# Shutdown_Circuit.net
KiCad netlist of a schematic drawn in EAGLE
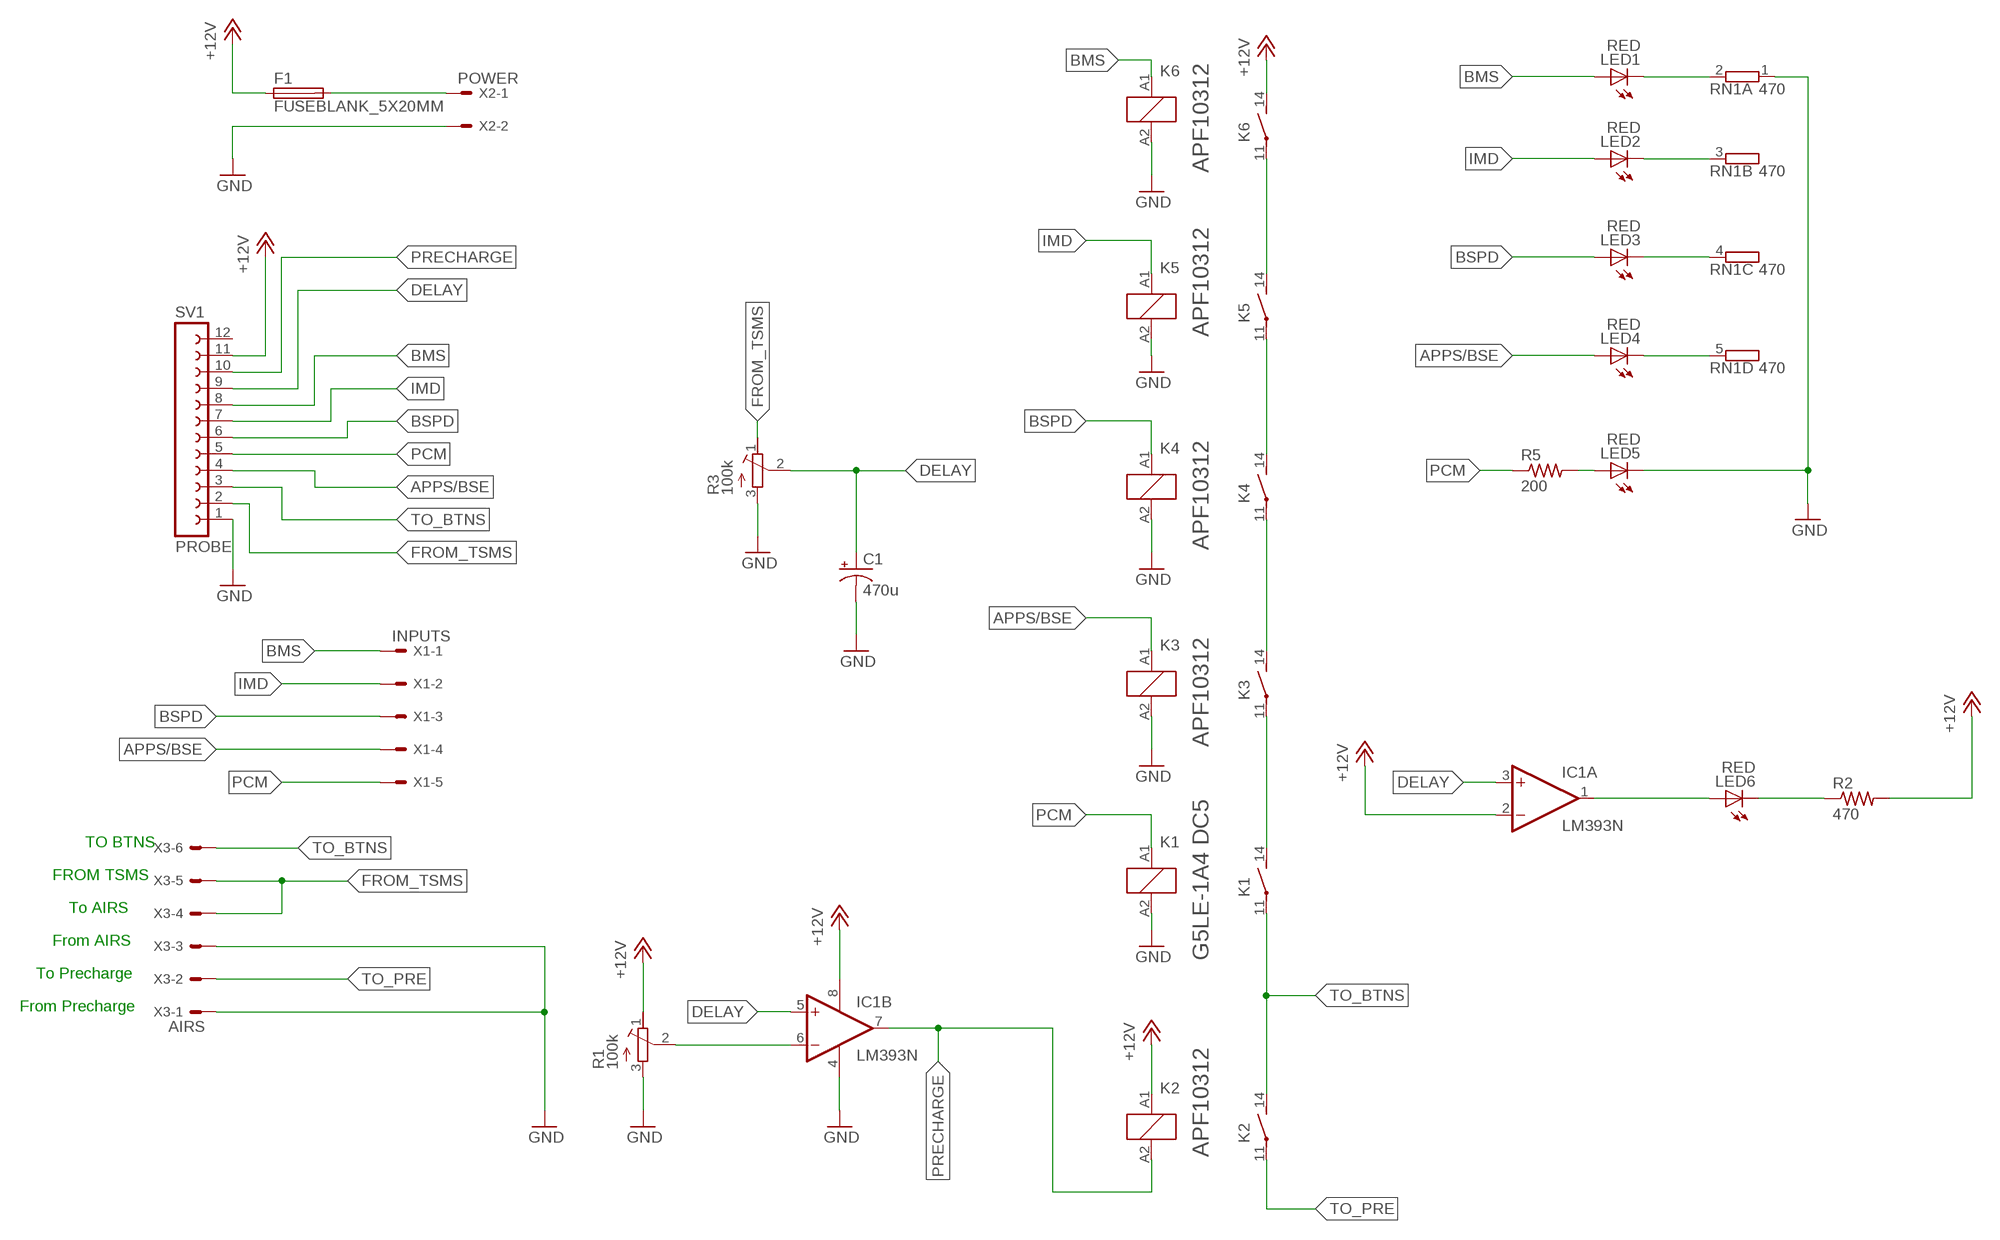
[diagram p0: schematic, sheet 1]

(export (version "E")
  (design (tool "Eeschema 10.0.6"))
  (components
    (comp (ref "C1")
      (value "470u")
      (footprint "eagle-import:E3,5-10")
      (libsource (lib "eagle-import") (part "CPOL-USE3.5-10"))
    )
    (comp (ref "F1")
      (value "FUSEBLANK_5X20MM")
      (footprint "eagle-import:FUSE_HOLDER_5X20MM")
      (libsource (lib "eagle-import") (part "FUSEBLANK_5X20MM"))
    )
    (comp (ref "IC1")
      (value "LM393N")
      (footprint "eagle-import:DIL08")
      (libsource (lib "eagle-import") (part "LM393N"))
    )
    (comp (ref "K1")
      (value "G5LE-1A4 DC5")
      (footprint "eagle-import:ZN1")
      (libsource (lib "eagle-import") (part "ZNS1106"))
    )
    (comp (ref "K2")
      (value "APF10312")
      (footprint "eagle-import:SNR-V1")
      (libsource (lib "eagle-import") (part "SNR1"))
    )
    (comp (ref "K3")
      (value "APF10312")
      (footprint "eagle-import:SNR-V1")
      (libsource (lib "eagle-import") (part "SNR1"))
    )
    (comp (ref "K4")
      (value "APF10312")
      (footprint "eagle-import:SNR-V1")
      (libsource (lib "eagle-import") (part "SNR1"))
    )
    (comp (ref "K5")
      (value "APF10312")
      (footprint "eagle-import:SNR-V1")
      (libsource (lib "eagle-import") (part "SNR1"))
    )
    (comp (ref "K6")
      (value "APF10312")
      (footprint "eagle-import:SNR-V1")
      (libsource (lib "eagle-import") (part "SNR1"))
    )
    (comp (ref "LED1")
      (value "RED")
      (footprint "eagle-import:LED5MM")
      (libsource (lib "eagle-import") (part "LED5MM"))
    )
    (comp (ref "LED2")
      (value "RED")
      (footprint "eagle-import:LED5MM")
      (libsource (lib "eagle-import") (part "LED5MM"))
    )
    (comp (ref "LED3")
      (value "RED")
      (footprint "eagle-import:LED5MM")
      (libsource (lib "eagle-import") (part "LED5MM"))
    )
    (comp (ref "LED4")
      (value "RED")
      (footprint "eagle-import:LED5MM")
      (libsource (lib "eagle-import") (part "LED5MM"))
    )
    (comp (ref "LED5")
      (value "RED")
      (footprint "eagle-import:LED5MM")
      (libsource (lib "eagle-import") (part "LED5MM"))
    )
    (comp (ref "LED6")
      (value "RED")
      (footprint "eagle-import:LED5MM")
      (libsource (lib "eagle-import") (part "LED5MM"))
    )
    (comp (ref "R1")
      (value "100k")
      (footprint "eagle-import:RTRIM3006P")
      (libsource (lib "eagle-import") (part "R-TRIMM3006P"))
    )
    (comp (ref "R2")
      (value "470")
      (footprint "eagle-import:0207_10")
      (libsource (lib "eagle-import") (part "R-US_0207/10"))
    )
    (comp (ref "R3")
      (value "100k")
      (footprint "eagle-import:RTRIM3006P")
      (libsource (lib "eagle-import") (part "R-TRIMM3006P"))
    )
    (comp (ref "R5")
      (value "200")
      (footprint "eagle-import:0207_10")
      (libsource (lib "eagle-import") (part "R-US_0207/10"))
    )
    (comp (ref "RN1")
      (value "470")
      (footprint "eagle-import:SIL5")
      (libsource (lib "eagle-import") (part "GE04R"))
    )
    (comp (ref "SV1")
      (value "PROBE")
      (footprint "eagle-import:FE12W")
      (libsource (lib "eagle-import") (part "FE12W"))
    )
    (comp (ref "X1")
      (value "INPUTS")
      (footprint "eagle-import:22-23-2051")
      (fields (field (name "MF") "MOLEX") (field (name "MPN") "22-23-2051"))
      (libsource (lib "eagle-import") (part "22-23-2051"))
    )
    (comp (ref "X2")
      (value "POWER")
      (footprint "eagle-import:22-23-2021")
      (fields (field (name "MF") "MOLEX") (field (name "MPN") "22-23-2021"))
      (libsource (lib "eagle-import") (part "22-23-2021"))
    )
    (comp (ref "X3")
      (value "AIRS")
      (footprint "eagle-import:22-23-2061")
      (fields (field (name "MF") "MOLEX") (field (name "MPN") "22-23-2061"))
      (libsource (lib "eagle-import") (part "22-23-2061"))
    )
  )
  (nets
    (net (code "1") (name "+12V") (class "Default")
      (node (ref "F1") (pin "1") (pinfunction "1_1") (pintype "passive"))
      (node (ref "IC1") (pin "2") (pinfunction "-IN_2") (pintype "input"))
      (node (ref "IC1") (pin "8") (pinfunction "V+_8") (pintype "power_in"))
      (node (ref "K2") (pin "A1") (pinfunction "1_A1") (pintype "passive"))
      (node (ref "K6") (pin "14") (pinfunction "S_14") (pintype "passive"))
      (node (ref "R1") (pin "1") (pinfunction "E_1") (pintype "passive"))
      (node (ref "R2") (pin "2") (pinfunction "2_2") (pintype "passive"))
      (node (ref "SV1") (pin "11") (pinfunction "11_11") (pintype "passive"))
    )
    (net (code "2") (name "APPS{slash}BSE") (class "Default")
      (node (ref "K3") (pin "A1") (pinfunction "1_A1") (pintype "passive"))
      (node (ref "LED4") (pin "A") (pinfunction "A_A") (pintype "passive"))
      (node (ref "SV1") (pin "4") (pinfunction "4_4") (pintype "passive"))
      (node (ref "X1") (pin "4") (pinfunction "S_4") (pintype "passive"))
    )
    (net (code "3") (name "BMS") (class "Default")
      (node (ref "K6") (pin "A1") (pinfunction "1_A1") (pintype "passive"))
      (node (ref "LED1") (pin "A") (pinfunction "A_A") (pintype "passive"))
      (node (ref "SV1") (pin "8") (pinfunction "8_8") (pintype "passive"))
      (node (ref "X1") (pin "1") (pinfunction "S_1") (pintype "passive"))
    )
    (net (code "4") (name "BSPD") (class "Default")
      (node (ref "K4") (pin "A1") (pinfunction "1_A1") (pintype "passive"))
      (node (ref "LED3") (pin "A") (pinfunction "A_A") (pintype "passive"))
      (node (ref "SV1") (pin "6") (pinfunction "6_6") (pintype "passive"))
      (node (ref "X1") (pin "3") (pinfunction "S_3") (pintype "passive"))
    )
    (net (code "5") (name "DELAY") (class "Default")
      (node (ref "C1") (pin "+") (pinfunction "+_+") (pintype "passive"))
      (node (ref "IC1") (pin "3") (pinfunction "+IN_3") (pintype "input"))
      (node (ref "IC1") (pin "5") (pinfunction "+IN_5") (pintype "input"))
      (node (ref "R3") (pin "2") (pinfunction "S_2") (pintype "passive"))
      (node (ref "SV1") (pin "9") (pinfunction "9_9") (pintype "passive"))
    )
    (net (code "6") (name "FROM_TSMS") (class "Default")
      (node (ref "R3") (pin "1") (pinfunction "E_1") (pintype "passive"))
      (node (ref "SV1") (pin "2") (pinfunction "2_2") (pintype "passive"))
      (node (ref "X3") (pin "4") (pinfunction "S_4") (pintype "passive"))
      (node (ref "X3") (pin "5") (pinfunction "S_5") (pintype "passive"))
    )
    (net (code "7") (name "GND") (class "Default")
      (node (ref "C1") (pin "-") (pinfunction "-_-") (pintype "passive"))
      (node (ref "IC1") (pin "4") (pinfunction "V-_4") (pintype "power_in"))
      (node (ref "K1") (pin "A2") (pinfunction "2_A2") (pintype "passive"))
      (node (ref "K3") (pin "A2") (pinfunction "2_A2") (pintype "passive"))
      (node (ref "K4") (pin "A2") (pinfunction "2_A2") (pintype "passive"))
      (node (ref "K5") (pin "A2") (pinfunction "2_A2") (pintype "passive"))
      (node (ref "K6") (pin "A2") (pinfunction "2_A2") (pintype "passive"))
      (node (ref "LED5") (pin "K") (pinfunction "C_K") (pintype "passive"))
      (node (ref "R1") (pin "3") (pinfunction "A_3") (pintype "passive"))
      (node (ref "R3") (pin "3") (pinfunction "A_3") (pintype "passive"))
      (node (ref "RN1") (pin "1") (pinfunction "1_1") (pintype "passive"))
      (node (ref "SV1") (pin "1") (pinfunction "1_1") (pintype "passive"))
      (node (ref "X2") (pin "2") (pinfunction "S_2") (pintype "passive"))
      (node (ref "X3") (pin "1") (pinfunction "S_1") (pintype "passive"))
      (node (ref "X3") (pin "3") (pinfunction "S_3") (pintype "passive"))
    )
    (net (code "8") (name "IMD") (class "Default")
      (node (ref "K5") (pin "A1") (pinfunction "1_A1") (pintype "passive"))
      (node (ref "LED2") (pin "A") (pinfunction "A_A") (pintype "passive"))
      (node (ref "SV1") (pin "7") (pinfunction "7_7") (pintype "passive"))
      (node (ref "X1") (pin "2") (pinfunction "S_2") (pintype "passive"))
    )
    (net (code "9") (name "Net-(IC1A-OUT)") (class "Default")
      (node (ref "IC1") (pin "1") (pinfunction "OUT_1") (pintype "output"))
      (node (ref "LED6") (pin "A") (pinfunction "A_A") (pintype "passive"))
    )
    (net (code "10") (name "Net-(IC1B--IN)") (class "Default")
      (node (ref "IC1") (pin "6") (pinfunction "-IN_6") (pintype "input"))
      (node (ref "R1") (pin "2") (pinfunction "S_2") (pintype "passive"))
    )
    (net (code "11") (name "Net-(K1B-S)") (class "Default")
      (node (ref "K1") (pin "14") (pinfunction "S_14") (pintype "passive"))
      (node (ref "K3") (pin "11") (pinfunction "P_11") (pintype "passive"))
    )
    (net (code "12") (name "Net-(K3B-S)") (class "Default")
      (node (ref "K3") (pin "14") (pinfunction "S_14") (pintype "passive"))
      (node (ref "K4") (pin "11") (pinfunction "P_11") (pintype "passive"))
    )
    (net (code "13") (name "Net-(K4B-S)") (class "Default")
      (node (ref "K4") (pin "14") (pinfunction "S_14") (pintype "passive"))
      (node (ref "K5") (pin "11") (pinfunction "P_11") (pintype "passive"))
    )
    (net (code "14") (name "Net-(K5B-S)") (class "Default")
      (node (ref "K5") (pin "14") (pinfunction "S_14") (pintype "passive"))
      (node (ref "K6") (pin "11") (pinfunction "P_11") (pintype "passive"))
    )
    (net (code "15") (name "Net-(LED1-C)") (class "Default")
      (node (ref "LED1") (pin "K") (pinfunction "C_K") (pintype "passive"))
      (node (ref "RN1") (pin "2") (pinfunction "2_2") (pintype "passive"))
    )
    (net (code "16") (name "Net-(LED2-C)") (class "Default")
      (node (ref "LED2") (pin "K") (pinfunction "C_K") (pintype "passive"))
      (node (ref "RN1") (pin "3") (pinfunction "2_3") (pintype "passive"))
    )
    (net (code "17") (name "Net-(LED3-C)") (class "Default")
      (node (ref "LED3") (pin "K") (pinfunction "C_K") (pintype "passive"))
      (node (ref "RN1") (pin "4") (pinfunction "2_4") (pintype "passive"))
    )
    (net (code "18") (name "Net-(LED4-C)") (class "Default")
      (node (ref "LED4") (pin "K") (pinfunction "C_K") (pintype "passive"))
      (node (ref "RN1") (pin "5") (pinfunction "2_5") (pintype "passive"))
    )
    (net (code "19") (name "Net-(LED5-PadA)") (class "Default")
      (node (ref "LED5") (pin "A") (pinfunction "A_A") (pintype "passive"))
      (node (ref "R5") (pin "2") (pinfunction "2_2") (pintype "passive"))
    )
    (net (code "20") (name "Net-(LED6-C)") (class "Default")
      (node (ref "LED6") (pin "K") (pinfunction "C_K") (pintype "passive"))
      (node (ref "R2") (pin "1") (pinfunction "1_1") (pintype "passive"))
    )
    (net (code "21") (name "Net-(X2A-S)") (class "Default")
      (node (ref "F1") (pin "2") (pinfunction "2_2") (pintype "passive"))
      (node (ref "X2") (pin "1") (pinfunction "S_1") (pintype "passive"))
    )
    (net (code "22") (name "PCM") (class "Default")
      (node (ref "K1") (pin "A1") (pinfunction "1_A1") (pintype "passive"))
      (node (ref "R5") (pin "1") (pinfunction "1_1") (pintype "passive"))
      (node (ref "SV1") (pin "5") (pinfunction "5_5") (pintype "passive"))
      (node (ref "X1") (pin "5") (pinfunction "S_5") (pintype "passive"))
    )
    (net (code "23") (name "PRECHARGE") (class "Default")
      (node (ref "IC1") (pin "7") (pinfunction "OUT_7") (pintype "output"))
      (node (ref "K2") (pin "A2") (pinfunction "2_A2") (pintype "passive"))
      (node (ref "SV1") (pin "10") (pinfunction "10_10") (pintype "passive"))
    )
    (net (code "24") (name "TO_BTNS") (class "Default")
      (node (ref "K1") (pin "11") (pinfunction "P_11") (pintype "passive"))
      (node (ref "K2") (pin "14") (pinfunction "S_14") (pintype "passive"))
      (node (ref "SV1") (pin "3") (pinfunction "3_3") (pintype "passive"))
      (node (ref "X3") (pin "6") (pinfunction "S_6") (pintype "passive"))
    )
    (net (code "25") (name "TO_PRE") (class "Default")
      (node (ref "K2") (pin "11") (pinfunction "P_11") (pintype "passive"))
      (node (ref "X3") (pin "2") (pinfunction "S_2") (pintype "passive"))
    )
    (net (code "26") (name "unconnected-(SV1-Pad12)") (class "Default")
      (node (ref "SV1") (pin "12") (pinfunction "12_12") (pintype "passive"))
    )
  )
)
